# KastlController.net
KiCad netlist of a schematic drawn in EAGLE
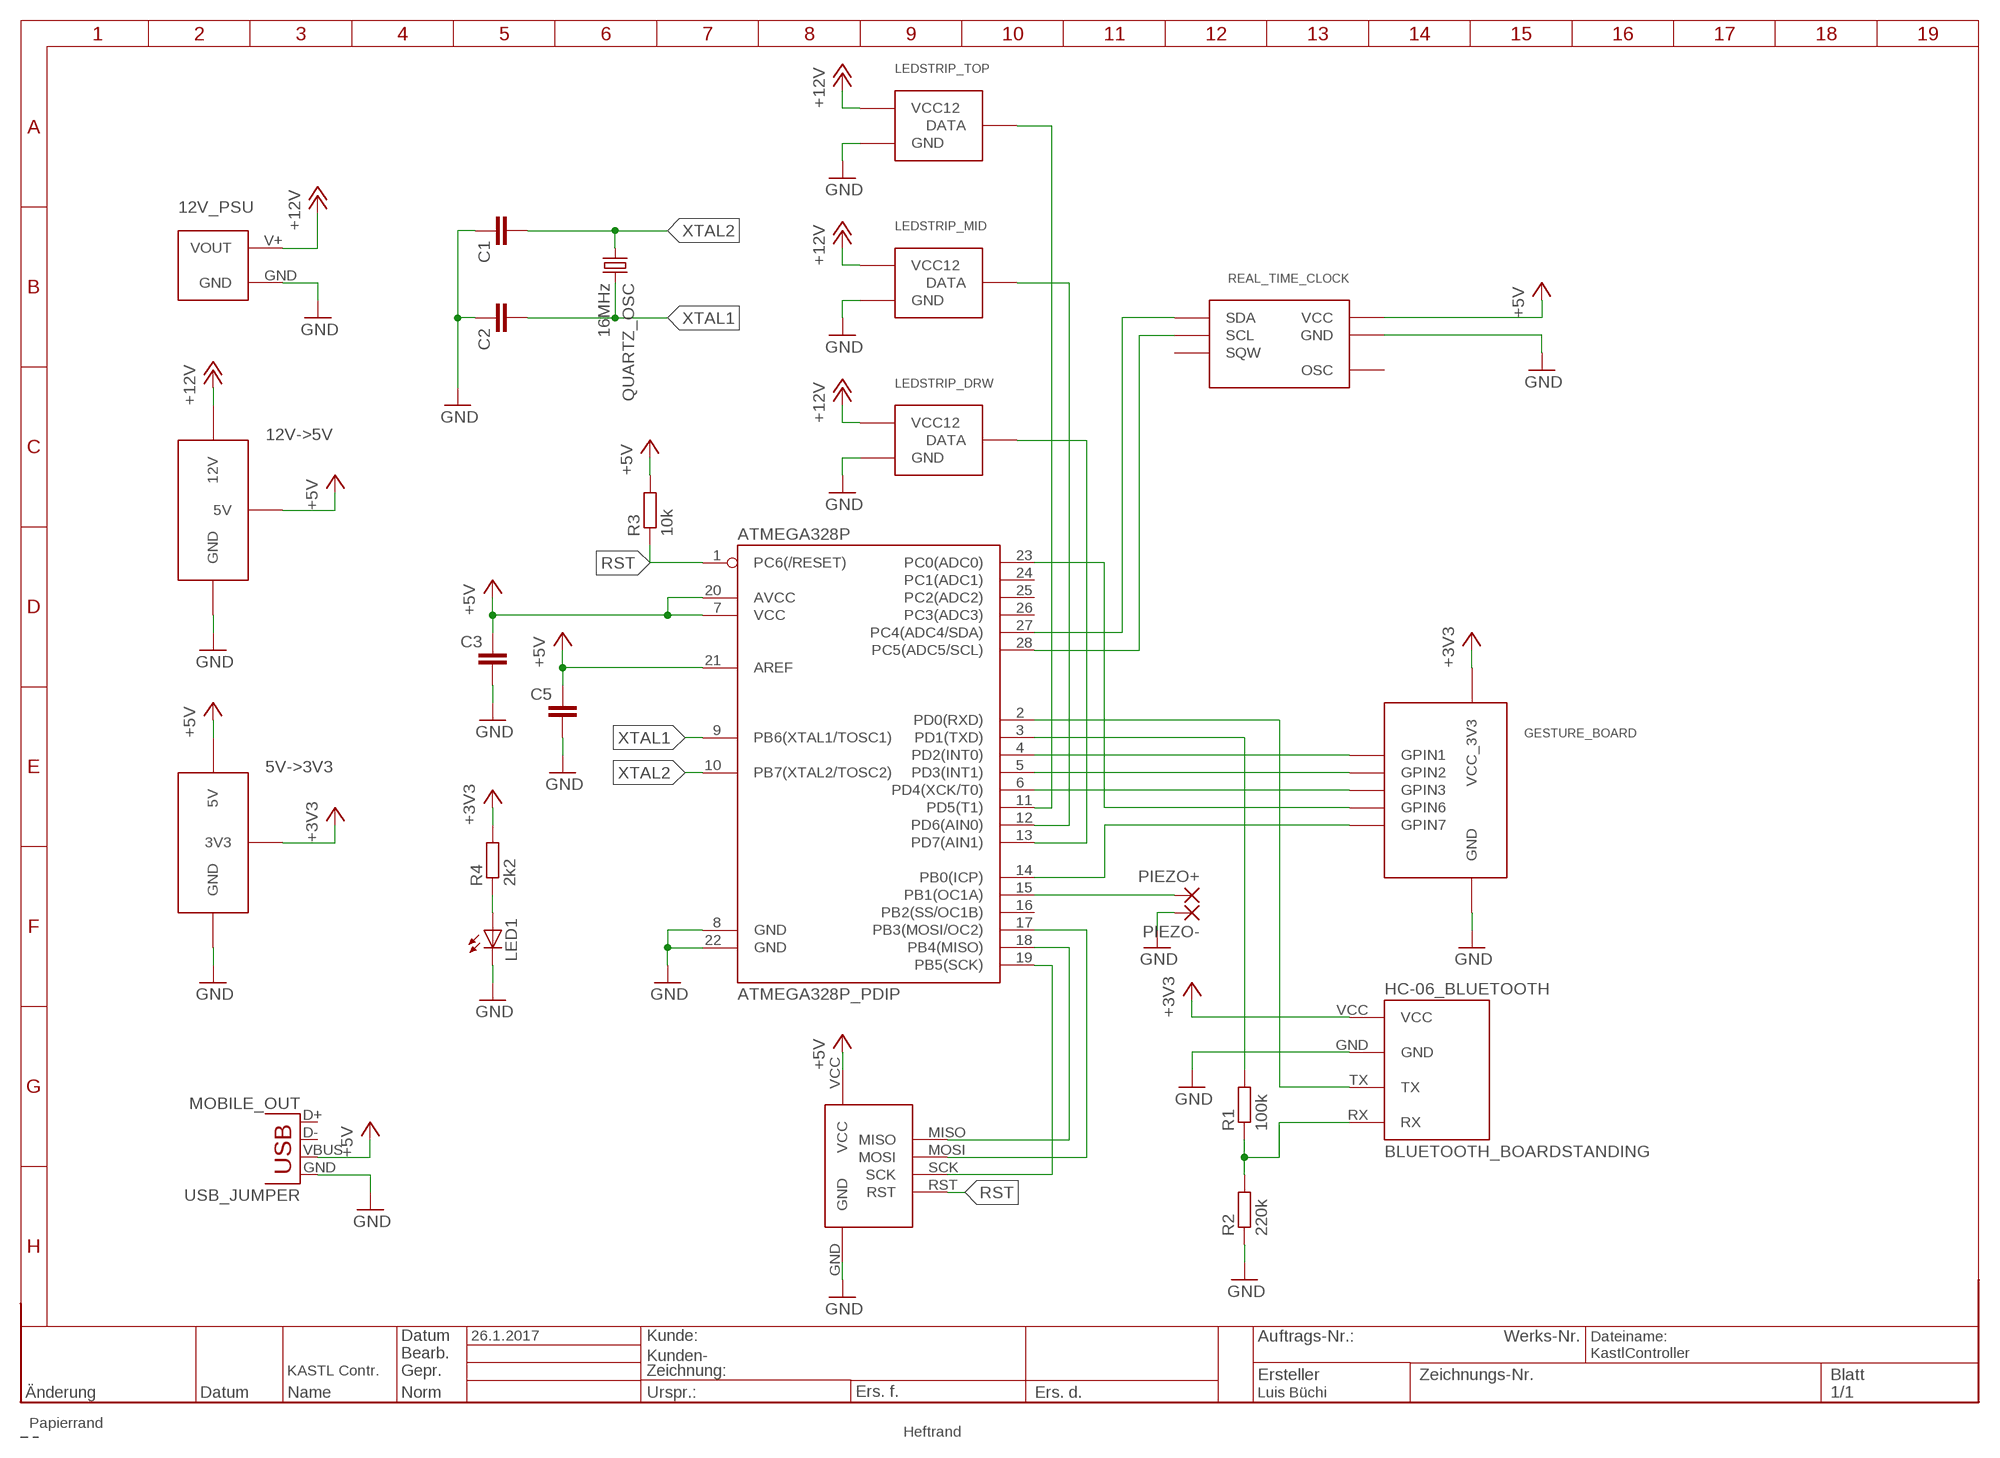
[diagram p0: schematic, sheet 1]

(export (version "E")
  (design (tool "Eeschema 10.0.6"))
  (components
    (comp (ref "5V->3V3")
      (value "VOLTAGE_REG_5V_3V3")
      (footprint "eagle-import:3_PIN_HEADER")
      (libsource (lib "eagle-import") (part "VOLTAGE_REG_5V_3V3"))
    )
    (comp (ref "12V->5V")
      (value "VOLTAGE_REG_12V_5V")
      (footprint "eagle-import:3_PIN_HEADER_BIG")
      (libsource (lib "eagle-import") (part "VOLTAGE_REG_12V_5V"))
    )
    (comp (ref "12V_PSU")
      (value "PWR_CONNECTOR")
      (footprint "eagle-import:2PIN_CONN")
      (libsource (lib "eagle-import") (part "PWR_CONNECTOR"))
    )
    (comp (ref "ATMEGA328P")
      (value "ATMEGA328P_PDIP")
      (footprint "eagle-import:DIL28-3")
      (libsource (lib "eagle-import") (part "ATMEGA328P_PDIP"))
    )
    (comp (ref "C1")
      (value "C-EU_025-024X044")
      (footprint "eagle-import:C2.5-2")
      (libsource (lib "eagle-import") (part "C-EU_025-024X044"))
    )
    (comp (ref "C2")
      (value "C-EU_025-024X044")
      (footprint "eagle-import:C2.5-2")
      (libsource (lib "eagle-import") (part "C-EU_025-024X044"))
    )
    (comp (ref "C3")
      (value "C-EU_025-024X044")
      (footprint "eagle-import:C2.5-2")
      (libsource (lib "eagle-import") (part "C-EU_025-024X044"))
    )
    (comp (ref "C5")
      (value "C-EU_025-024X044")
      (footprint "eagle-import:C2.5-2")
      (libsource (lib "eagle-import") (part "C-EU_025-024X044"))
    )
    (comp (ref "GESTURE_BOARD")
      (value "GESTUREBOARD")
      (footprint "eagle-import:INTERFACE_AND_POWER_CONN")
      (libsource (lib "eagle-import") (part "GESTUREBOARD"))
    )
    (comp (ref "HC-06_BLUETOOTH")
      (value "BLUETOOTH_BOARDSTANDING")
      (footprint "eagle-import:BT_BOARD_FOOTPRINT_STANDING")
      (libsource (lib "eagle-import") (part "BLUETOOTH_BOARDSTANDING"))
    )
    (comp (ref "LED1")
      (value "LEDS_5MM")
      (footprint "eagle-import:LED5MM")
      (libsource (lib "eagle-import") (part "LEDS_5MM"))
    )
    (comp (ref "LEDSTRIP_DRW")
      (value "WS2812_JMP")
      (footprint "eagle-import:WS2812_JUMPER")
      (libsource (lib "eagle-import") (part "WS2812_JMP"))
    )
    (comp (ref "LEDSTRIP_MID")
      (value "WS2812_JMP")
      (footprint "eagle-import:WS2812_JUMPER")
      (libsource (lib "eagle-import") (part "WS2812_JMP"))
    )
    (comp (ref "LEDSTRIP_TOP")
      (value "WS2812_JMP")
      (footprint "eagle-import:WS2812_JUMPER")
      (libsource (lib "eagle-import") (part "WS2812_JMP"))
    )
    (comp (ref "MOBILE_OUT")
      (value "USB_JUMPER")
      (footprint "eagle-import:USB_JUMPER")
      (libsource (lib "eagle-import") (part "USB_JUMPER"))
    )
    (comp (ref "PIEZO+")
      (value "1,6/0,9")
      (footprint "eagle-import:1,6_0,9")
      (libsource (lib "eagle-import") (part "1,6/0,9"))
    )
    (comp (ref "PIEZO-")
      (value "1,6/0,9")
      (footprint "eagle-import:1,6_0,9")
      (libsource (lib "eagle-import") (part "1,6/0,9"))
    )
    (comp (ref "QUARTZ_OSC")
      (value "16MHz")
      (footprint "eagle-import:HC33U-V")
      (libsource (lib "eagle-import") (part "CRYSTALHC33U-V"))
    )
    (comp (ref "R1")
      (value "100k")
      (footprint "eagle-import:R-2,5")
      (libsource (lib "eagle-import") (part "R-EU_0204/2V"))
    )
    (comp (ref "R2")
      (value "220k")
      (footprint "eagle-import:R-2,5")
      (libsource (lib "eagle-import") (part "R-EU_0204/2V"))
    )
    (comp (ref "R3")
      (value "10k")
      (footprint "eagle-import:R-2,5")
      (libsource (lib "eagle-import") (part "R-EU_0204/2V"))
    )
    (comp (ref "R4")
      (value "2k2")
      (footprint "eagle-import:R-2,5")
      (libsource (lib "eagle-import") (part "R-EU_0204/2V"))
    )
    (comp (ref "REAL_TIME_CLOCK")
      (value "DS3231_RTC_MODULE")
      (footprint "eagle-import:6P_HEADER")
      (libsource (lib "eagle-import") (part "DS3231_RTC_MODULE"))
    )
    (comp (ref "U$1")
      (value "INTEGRATED_PROGRAMMING_INTERFACE")
      (footprint "eagle-import:6PIN_HEADER")
      (libsource (lib "eagle-import") (part "INTEGRATED_PROGRAMMING_INTERFACE"))
    )
  )
  (nets
    (net (code "1") (name "+3V3") (class "Default")
      (node (ref "5V->3V3") (pin "PIN2") (pinfunction "3V3_PIN2") (pintype "bidirectional"))
      (node (ref "GESTURE_BOARD") (pin "VCC_3V3") (pinfunction "VCC_3V3_VCC_3V3") (pintype "bidirectional"))
      (node (ref "HC-06_BLUETOOTH") (pin "VCC") (pinfunction "VCC_VCC") (pintype "bidirectional"))
      (node (ref "R4") (pin "2") (pinfunction "2_2") (pintype "passive"))
    )
    (net (code "2") (name "+5V") (class "Default")
      (node (ref "12V->5V") (pin "PIN1") (pinfunction "5V_PIN1") (pintype "bidirectional"))
      (node (ref "5V->3V3") (pin "PIN1") (pinfunction "5V_PIN1") (pintype "bidirectional"))
      (node (ref "ATMEGA328P") (pin "20") (pinfunction "AVCC_20") (pintype "bidirectional"))
      (node (ref "ATMEGA328P") (pin "21") (pinfunction "AREF_21") (pintype "bidirectional"))
      (node (ref "ATMEGA328P") (pin "7") (pinfunction "VCC_7") (pintype "bidirectional"))
      (node (ref "C3") (pin "1") (pinfunction "1_1") (pintype "passive"))
      (node (ref "C5") (pin "1") (pinfunction "1_1") (pintype "passive"))
      (node (ref "MOBILE_OUT") (pin "VBUS") (pinfunction "VBUS_VBUS") (pintype "bidirectional"))
      (node (ref "R3") (pin "2") (pinfunction "2_2") (pintype "passive"))
      (node (ref "REAL_TIME_CLOCK") (pin "VCC") (pinfunction "VCC_VCC") (pintype "bidirectional"))
      (node (ref "U$1") (pin "VCC") (pinfunction "VCC_VCC") (pintype "bidirectional"))
    )
    (net (code "3") (name "+12V") (class "Default")
      (node (ref "12V->5V") (pin "PIN3") (pinfunction "12V_PIN3") (pintype "bidirectional"))
      (node (ref "12V_PSU") (pin "V+") (pinfunction "VOUT_V+") (pintype "bidirectional"))
      (node (ref "LEDSTRIP_DRW") (pin "VCC12") (pinfunction "VCC12_VCC12") (pintype "bidirectional"))
      (node (ref "LEDSTRIP_MID") (pin "VCC12") (pinfunction "VCC12_VCC12") (pintype "bidirectional"))
      (node (ref "LEDSTRIP_TOP") (pin "VCC12") (pinfunction "VCC12_VCC12") (pintype "bidirectional"))
    )
    (net (code "4") (name "GND") (class "Default")
      (node (ref "12V->5V") (pin "PIN2") (pinfunction "GND_PIN2") (pintype "bidirectional"))
      (node (ref "12V_PSU") (pin "GND") (pinfunction "GND_GND") (pintype "bidirectional"))
      (node (ref "5V->3V3") (pin "PIN3") (pinfunction "GND_PIN3") (pintype "bidirectional"))
      (node (ref "ATMEGA328P") (pin "22") (pinfunction "GND_22") (pintype "bidirectional"))
      (node (ref "ATMEGA328P") (pin "8") (pinfunction "GND_8") (pintype "bidirectional"))
      (node (ref "C1") (pin "1") (pinfunction "1_1") (pintype "passive"))
      (node (ref "C2") (pin "1") (pinfunction "1_1") (pintype "passive"))
      (node (ref "C3") (pin "2") (pinfunction "2_2") (pintype "passive"))
      (node (ref "C5") (pin "2") (pinfunction "2_2") (pintype "passive"))
      (node (ref "GESTURE_BOARD") (pin "GND") (pinfunction "GND_GND") (pintype "bidirectional"))
      (node (ref "HC-06_BLUETOOTH") (pin "GND") (pinfunction "GND_GND") (pintype "bidirectional"))
      (node (ref "LED1") (pin "K") (pinfunction "C_K") (pintype "passive"))
      (node (ref "LEDSTRIP_DRW") (pin "GND1") (pinfunction "GND_GND1") (pintype "bidirectional"))
      (node (ref "LEDSTRIP_DRW") (pin "GND2") (pinfunction "GND_GND2") (pintype "bidirectional"))
      (node (ref "LEDSTRIP_MID") (pin "GND1") (pinfunction "GND_GND1") (pintype "bidirectional"))
      (node (ref "LEDSTRIP_MID") (pin "GND2") (pinfunction "GND_GND2") (pintype "bidirectional"))
      (node (ref "LEDSTRIP_TOP") (pin "GND1") (pinfunction "GND_GND1") (pintype "bidirectional"))
      (node (ref "LEDSTRIP_TOP") (pin "GND2") (pinfunction "GND_GND2") (pintype "bidirectional"))
      (node (ref "MOBILE_OUT") (pin "GND") (pinfunction "GND_GND") (pintype "bidirectional"))
      (node (ref "PIEZO-") (pin "1") (pinfunction "P_1") (pintype "passive"))
      (node (ref "R2") (pin "1") (pinfunction "1_1") (pintype "passive"))
      (node (ref "REAL_TIME_CLOCK") (pin "GND") (pinfunction "GND_GND") (pintype "bidirectional"))
      (node (ref "U$1") (pin "GND") (pinfunction "GND_GND") (pintype "bidirectional"))
    )
    (net (code "5") (name "Net-(ATMEGA328P-PB0(ICP))") (class "Default")
      (node (ref "ATMEGA328P") (pin "14") (pinfunction "PB0(ICP)_14") (pintype "bidirectional"))
      (node (ref "GESTURE_BOARD") (pin "GPIN7") (pinfunction "GPIN7_GPIN7") (pintype "bidirectional"))
    )
    (net (code "6") (name "Net-(ATMEGA328P-PB1(OC1A))") (class "Default")
      (node (ref "ATMEGA328P") (pin "15") (pinfunction "PB1(OC1A)_15") (pintype "bidirectional"))
      (node (ref "PIEZO+") (pin "1") (pinfunction "P_1") (pintype "passive"))
    )
    (net (code "7") (name "Net-(ATMEGA328P-PB3(MOSI{slash}OC2))") (class "Default")
      (node (ref "ATMEGA328P") (pin "17") (pinfunction "PB3(MOSI/OC2)_17") (pintype "bidirectional"))
      (node (ref "U$1") (pin "MOSI") (pinfunction "MOSI_MOSI") (pintype "bidirectional"))
    )
    (net (code "8") (name "Net-(ATMEGA328P-PB4(MISO))") (class "Default")
      (node (ref "ATMEGA328P") (pin "18") (pinfunction "PB4(MISO)_18") (pintype "bidirectional"))
      (node (ref "U$1") (pin "MISO") (pinfunction "MISO_MISO") (pintype "bidirectional"))
    )
    (net (code "9") (name "Net-(ATMEGA328P-PB5(SCK))") (class "Default")
      (node (ref "ATMEGA328P") (pin "19") (pinfunction "PB5(SCK)_19") (pintype "bidirectional"))
      (node (ref "U$1") (pin "SCK") (pinfunction "SCK_SCK") (pintype "bidirectional"))
    )
    (net (code "10") (name "Net-(ATMEGA328P-PC0(ADC0))") (class "Default")
      (node (ref "ATMEGA328P") (pin "23") (pinfunction "PC0(ADC0)_23") (pintype "bidirectional"))
      (node (ref "GESTURE_BOARD") (pin "GPIN6") (pinfunction "GPIN6_GPIN6") (pintype "bidirectional"))
    )
    (net (code "11") (name "Net-(ATMEGA328P-PC4(ADC4{slash}SDA))") (class "Default")
      (node (ref "ATMEGA328P") (pin "27") (pinfunction "PC4(ADC4/SDA)_27") (pintype "bidirectional"))
      (node (ref "REAL_TIME_CLOCK") (pin "SDA") (pinfunction "SDA_SDA") (pintype "bidirectional"))
    )
    (net (code "12") (name "Net-(ATMEGA328P-PC5(ADC5{slash}SCL))") (class "Default")
      (node (ref "ATMEGA328P") (pin "28") (pinfunction "PC5(ADC5/SCL)_28") (pintype "bidirectional"))
      (node (ref "REAL_TIME_CLOCK") (pin "SCL") (pinfunction "SCL_SCL") (pintype "bidirectional"))
    )
    (net (code "13") (name "Net-(ATMEGA328P-PD0(RXD))") (class "Default")
      (node (ref "ATMEGA328P") (pin "2") (pinfunction "PD0(RXD)_2") (pintype "bidirectional"))
      (node (ref "HC-06_BLUETOOTH") (pin "TX") (pinfunction "TX_TX") (pintype "bidirectional"))
    )
    (net (code "14") (name "Net-(ATMEGA328P-PD1(TXD))") (class "Default")
      (node (ref "ATMEGA328P") (pin "3") (pinfunction "PD1(TXD)_3") (pintype "bidirectional"))
      (node (ref "R1") (pin "2") (pinfunction "2_2") (pintype "passive"))
    )
    (net (code "15") (name "Net-(ATMEGA328P-PD2(INT0))") (class "Default")
      (node (ref "ATMEGA328P") (pin "4") (pinfunction "PD2(INT0)_4") (pintype "bidirectional"))
      (node (ref "GESTURE_BOARD") (pin "GPIN1") (pinfunction "GPIN1_GPIN1") (pintype "bidirectional"))
    )
    (net (code "16") (name "Net-(ATMEGA328P-PD3(INT1))") (class "Default")
      (node (ref "ATMEGA328P") (pin "5") (pinfunction "PD3(INT1)_5") (pintype "bidirectional"))
      (node (ref "GESTURE_BOARD") (pin "GPIN2") (pinfunction "GPIN2_GPIN2") (pintype "bidirectional"))
    )
    (net (code "17") (name "Net-(ATMEGA328P-PD4(XCK{slash}T0))") (class "Default")
      (node (ref "ATMEGA328P") (pin "6") (pinfunction "PD4(XCK/T0)_6") (pintype "bidirectional"))
      (node (ref "GESTURE_BOARD") (pin "GPIN3") (pinfunction "GPIN3_GPIN3") (pintype "bidirectional"))
    )
    (net (code "18") (name "Net-(ATMEGA328P-PD5(T1))") (class "Default")
      (node (ref "ATMEGA328P") (pin "11") (pinfunction "PD5(T1)_11") (pintype "bidirectional"))
      (node (ref "LEDSTRIP_TOP") (pin "DATA") (pinfunction "DATA_DATA") (pintype "bidirectional"))
    )
    (net (code "19") (name "Net-(ATMEGA328P-PD6(AIN0))") (class "Default")
      (node (ref "ATMEGA328P") (pin "12") (pinfunction "PD6(AIN0)_12") (pintype "bidirectional"))
      (node (ref "LEDSTRIP_MID") (pin "DATA") (pinfunction "DATA_DATA") (pintype "bidirectional"))
    )
    (net (code "20") (name "Net-(ATMEGA328P-PD7(AIN1))") (class "Default")
      (node (ref "ATMEGA328P") (pin "13") (pinfunction "PD7(AIN1)_13") (pintype "bidirectional"))
      (node (ref "LEDSTRIP_DRW") (pin "DATA") (pinfunction "DATA_DATA") (pintype "bidirectional"))
    )
    (net (code "21") (name "Net-(HC-06_BLUETOOTH-PadRX)") (class "Default")
      (node (ref "HC-06_BLUETOOTH") (pin "RX") (pinfunction "RX_RX") (pintype "bidirectional"))
      (node (ref "R1") (pin "1") (pinfunction "1_1") (pintype "passive"))
      (node (ref "R2") (pin "2") (pinfunction "2_2") (pintype "passive"))
    )
    (net (code "22") (name "Net-(LED1-PadA)") (class "Default")
      (node (ref "LED1") (pin "A") (pinfunction "A_A") (pintype "passive"))
      (node (ref "R4") (pin "1") (pinfunction "1_1") (pintype "passive"))
    )
    (net (code "23") (name "RST") (class "Default")
      (node (ref "ATMEGA328P") (pin "1") (pinfunction "PC6(/RESET)_1") (pintype "bidirectional"))
      (node (ref "R3") (pin "1") (pinfunction "1_1") (pintype "passive"))
      (node (ref "U$1") (pin "RST") (pinfunction "RST_RST") (pintype "bidirectional"))
    )
    (net (code "24") (name "XTAL1") (class "Default")
      (node (ref "ATMEGA328P") (pin "9") (pinfunction "PB6(XTAL1/TOSC1)_9") (pintype "bidirectional"))
      (node (ref "C2") (pin "2") (pinfunction "2_2") (pintype "passive"))
      (node (ref "QUARTZ_OSC") (pin "2") (pinfunction "2_2") (pintype "passive"))
    )
    (net (code "25") (name "XTAL2") (class "Default")
      (node (ref "ATMEGA328P") (pin "10") (pinfunction "PB7(XTAL2/TOSC2)_10") (pintype "bidirectional"))
      (node (ref "C1") (pin "2") (pinfunction "2_2") (pintype "passive"))
      (node (ref "QUARTZ_OSC") (pin "1") (pinfunction "1_1") (pintype "passive"))
    )
    (net (code "26") (name "unconnected-(ATMEGA328P-PB2(SS{slash}OC1B)-Pad16)") (class "Default")
      (node (ref "ATMEGA328P") (pin "16") (pinfunction "PB2(SS/OC1B)_16") (pintype "bidirectional"))
    )
    (net (code "27") (name "unconnected-(ATMEGA328P-PC1(ADC1)-Pad24)") (class "Default")
      (node (ref "ATMEGA328P") (pin "24") (pinfunction "PC1(ADC1)_24") (pintype "bidirectional"))
    )
    (net (code "28") (name "unconnected-(ATMEGA328P-PC2(ADC2)-Pad25)") (class "Default")
      (node (ref "ATMEGA328P") (pin "25") (pinfunction "PC2(ADC2)_25") (pintype "bidirectional"))
    )
    (net (code "29") (name "unconnected-(ATMEGA328P-PC3(ADC3)-Pad26)") (class "Default")
      (node (ref "ATMEGA328P") (pin "26") (pinfunction "PC3(ADC3)_26") (pintype "bidirectional"))
    )
    (net (code "30") (name "unconnected-(MOBILE_OUT-PadD+)") (class "Default")
      (node (ref "MOBILE_OUT") (pin "D+") (pinfunction "D+_D+") (pintype "bidirectional"))
    )
    (net (code "31") (name "unconnected-(MOBILE_OUT-PadD-)") (class "Default")
      (node (ref "MOBILE_OUT") (pin "D-") (pinfunction "D-_D-") (pintype "bidirectional"))
    )
    (net (code "32") (name "unconnected-(REAL_TIME_CLOCK-PadOSC)") (class "Default")
      (node (ref "REAL_TIME_CLOCK") (pin "OSC") (pinfunction "OSC_OSC") (pintype "bidirectional"))
    )
    (net (code "33") (name "unconnected-(REAL_TIME_CLOCK-PadSQW)") (class "Default")
      (node (ref "REAL_TIME_CLOCK") (pin "SQW") (pinfunction "SQW_SQW") (pintype "bidirectional"))
    )
  )
)
